# PCB.net
KiCad netlist of a schematic drawn in Altium Designer
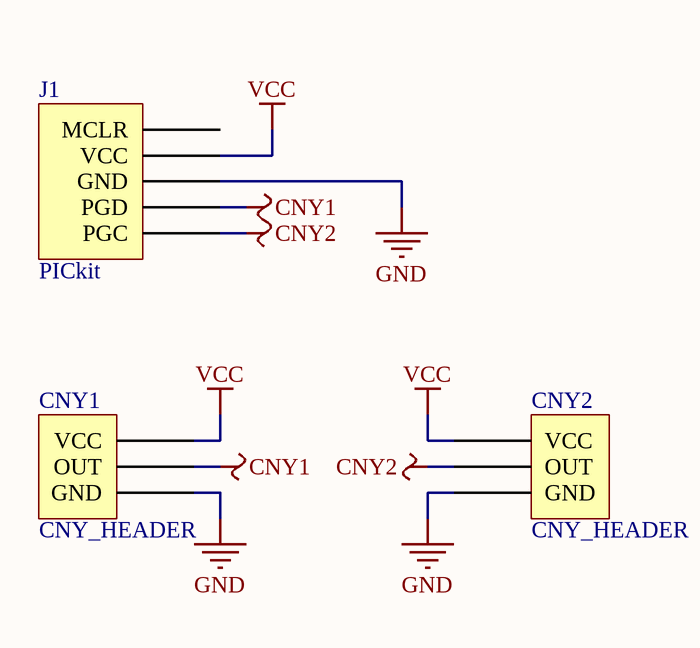
[diagram p0: PCB.SchDoc]

(export (version "E")
  (design (tool "Eeschema 10.0.6"))
  (components
    (comp (ref "CNY1")
      (value "CNY_HEADER")
      (footprint "CNY_HEADER")
      (libsource (lib "") (part "CNY_HEADER_1"))
    )
    (comp (ref "CNY2")
      (value "CNY_HEADER")
      (footprint "CNY_HEADER")
      (libsource (lib "AltiumLibraryOld") (part "CNY_HEADER"))
    )
    (comp (ref "J1")
      (value "PICkit")
      (footprint "Header 1x5")
      (libsource (lib "AltiumLibrary") (part "PICkit"))
    )
  )
  (nets
    (net (code "1") (name "CNY1") (class "Default")
      (node (ref "CNY1") (pin "3") (pinfunction "OUT_3") (pintype "passive"))
      (node (ref "J1") (pin "4") (pinfunction "PGD_4") (pintype "passive"))
    )
    (net (code "2") (name "CNY2") (class "Default")
      (node (ref "CNY2") (pin "3") (pinfunction "OUT_3") (pintype "passive"))
      (node (ref "J1") (pin "5") (pinfunction "PGC_5") (pintype "passive"))
    )
    (net (code "3") (name "GND") (class "Default")
      (node (ref "CNY1") (pin "1") (pinfunction "GND_1") (pintype "passive"))
      (node (ref "CNY2") (pin "1") (pinfunction "GND_1") (pintype "passive"))
      (node (ref "J1") (pin "3") (pinfunction "GND_3") (pintype "power_in"))
    )
    (net (code "4") (name "VCC") (class "Default")
      (node (ref "CNY1") (pin "2") (pinfunction "VCC_2") (pintype "passive"))
      (node (ref "CNY2") (pin "2") (pinfunction "VCC_2") (pintype "passive"))
      (node (ref "J1") (pin "2") (pinfunction "VCC_2") (pintype "power_in"))
    )
    (net (code "5") (name "unconnected-(J1-MCLR-Pad1)") (class "Default")
      (node (ref "J1") (pin "1") (pinfunction "MCLR_1") (pintype "passive"))
    )
  )
)
